# TD_0002-100.net
KiCad netlist of a schematic drawn in Altium Designer
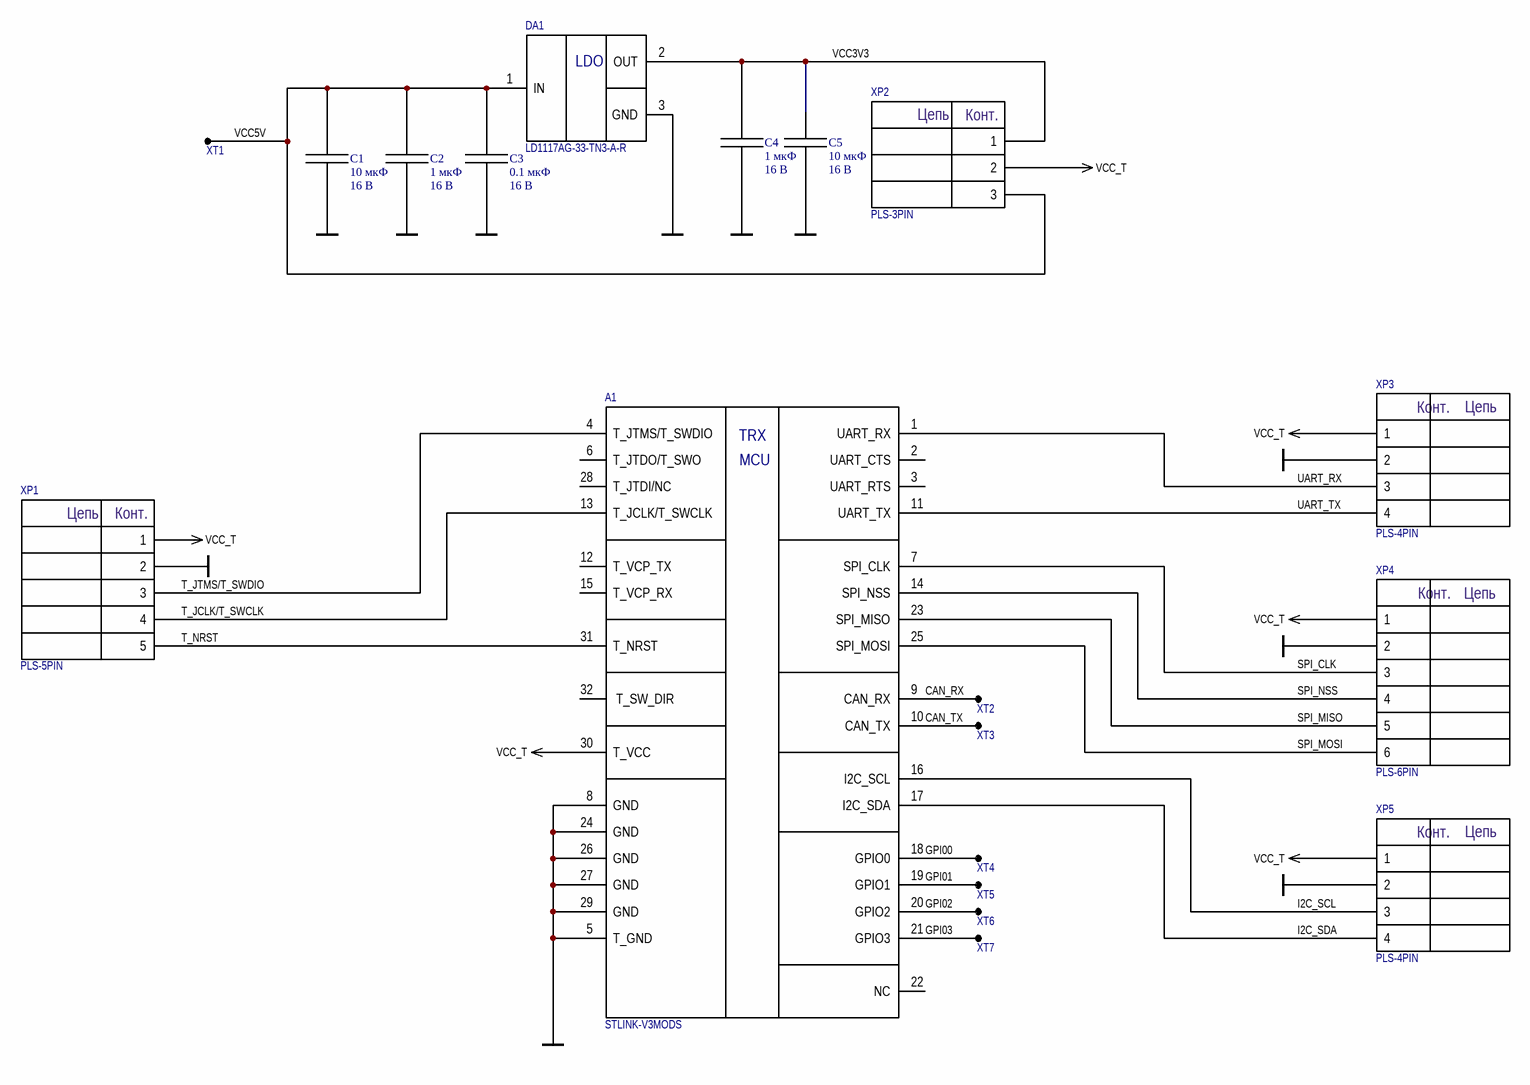
[diagram p0: TD.0002-100.SchDoc]

(export (version "E")
  (design (tool "Eeschema 10.0.6"))
  (components
    (comp (ref "A1")
      (value "STLINK-V3MODS")
      (footprint "STLINK-V3MODS")
      (description "Mini debuggers/programmers for STM32")
      (libsource (lib "FirstLib") (part "STLINK-V3MODS"))
    )
    (comp (ref "C1")
      (value "10 мкФ")
      (footprint "C_0603")
      (description "Chip Monolithic Ceramic Capacitor")
      (fields
        (field (name "PART NUMBER") "GRM188R61C106KAALD")
        (field (name "MANUFACTURER") "Murata")
        (field (name "VOLTAGE") "16 В")
      )
      (libsource (lib "Database_Libs") (part "Capacitor"))
    )
    (comp (ref "C2")
      (value "1 мкФ")
      (footprint "C_0402")
      (description "Chip Multilayer Ceramic Capacitors")
      (fields
        (field (name "PART NUMBER") "GRM155R61C105KA12D")
        (field (name "MANUFACTURER") "Murata")
        (field (name "VOLTAGE") "16 В")
      )
      (libsource (lib "Database_Libs") (part "Capacitor"))
    )
    (comp (ref "C3")
      (value "0.1 мкФ")
      (footprint "C_0402")
      (description "Chip Multilayer Ceramic Capacitors")
      (fields
        (field (name "PART NUMBER") "GRM155R71C104KA88D")
        (field (name "MANUFACTURER") "Murata")
        (field (name "VOLTAGE") "16 В")
      )
      (libsource (lib "Database_Libs") (part "Capacitor"))
    )
    (comp (ref "C4")
      (value "1 мкФ")
      (footprint "C_0402")
      (description "Chip Multilayer Ceramic Capacitors")
      (fields
        (field (name "PART NUMBER") "GRM155R61C105KA12D")
        (field (name "MANUFACTURER") "Murata")
        (field (name "VOLTAGE") "16 В")
      )
      (libsource (lib "Database_Libs") (part "Capacitor"))
    )
    (comp (ref "C5")
      (value "10 мкФ")
      (footprint "C_0603")
      (description "Chip Monolithic Ceramic Capacitor")
      (fields
        (field (name "PART NUMBER") "GRM188R61C106KAALD")
        (field (name "MANUFACTURER") "Murata")
        (field (name "VOLTAGE") "16 В")
      )
      (libsource (lib "Database_Libs") (part "Capacitor"))
    )
    (comp (ref "DA1")
      (value "LD1117AG-33-TN3-A-R")
      (footprint "TO-252")
      (description "Low drop fixed and adjustable positive voltage regulators")
      (libsource (lib "FirstLib") (part "LD1117AG-33-TN3-A-R"))
    )
    (comp (ref "XP1")
      (value "PLS-5PIN")
      (footprint "PLS-5PIN")
      (libsource (lib "FirstLib") (part "PLS-5PIN"))
    )
    (comp (ref "XP2")
      (value "PLS-3PIN")
      (footprint "PLS-3PIN")
      (libsource (lib "FirstLib") (part "PLS-3PIN"))
    )
    (comp (ref "XP3")
      (value "PLS-4PIN")
      (footprint "PLS-4PIN")
      (libsource (lib "FirstLib") (part "PLS-4PIN"))
    )
    (comp (ref "XP4")
      (value "PLS-6PIN")
      (footprint "PLS-6PIN")
      (libsource (lib "FirstLib") (part "PLS-6PIN"))
    )
    (comp (ref "XP5")
      (value "PLS-4PIN")
      (footprint "PLS-4PIN")
      (libsource (lib "FirstLib") (part "PLS-4PIN"))
    )
    (comp (ref "XT1")
      (value "pad")
      (footprint "FirstLib:PAD_2X2mm")
      (libsource (lib "FirstLib") (part "pad"))
    )
    (comp (ref "XT2") (value "pad") (footprint "pad_3x1mm") (libsource (lib "FirstLib") (part "pad")))
    (comp (ref "XT3") (value "pad") (footprint "pad_3x1mm") (libsource (lib "FirstLib") (part "pad")))
    (comp (ref "XT4") (value "pad") (footprint "pad_3x1mm") (libsource (lib "FirstLib") (part "pad")))
    (comp (ref "XT5") (value "pad") (footprint "pad_3x1mm") (libsource (lib "FirstLib") (part "pad")))
    (comp (ref "XT6") (value "pad") (footprint "pad_3x1mm") (libsource (lib "FirstLib") (part "pad")))
    (comp (ref "XT7") (value "pad") (footprint "pad_3x1mm") (libsource (lib "FirstLib") (part "pad")))
  )
  (nets
    (net (code "1") (name "/CAN_RX") (class "Default")
      (node (ref "A1") (pin "9") (pinfunction "CAN_RX_9") (pintype "passive"))
      (node (ref "XT2") (pin "1") (pinfunction "1_1") (pintype "passive"))
    )
    (net (code "2") (name "/CAN_TX") (class "Default")
      (node (ref "A1") (pin "10") (pinfunction "CAN_TX_10") (pintype "passive"))
      (node (ref "XT3") (pin "1") (pinfunction "1_1") (pintype "passive"))
    )
    (net (code "3") (name "/GPI00") (class "Default")
      (node (ref "A1") (pin "18") (pinfunction "GPIO0_18") (pintype "passive"))
      (node (ref "XT4") (pin "1") (pinfunction "1_1") (pintype "passive"))
    )
    (net (code "4") (name "/GPI01") (class "Default")
      (node (ref "A1") (pin "19") (pinfunction "GPIO1_19") (pintype "passive"))
      (node (ref "XT5") (pin "1") (pinfunction "1_1") (pintype "passive"))
    )
    (net (code "5") (name "/GPI02") (class "Default")
      (node (ref "A1") (pin "20") (pinfunction "GPIO2_20") (pintype "passive"))
      (node (ref "XT6") (pin "1") (pinfunction "1_1") (pintype "passive"))
    )
    (net (code "6") (name "/GPI03") (class "Default")
      (node (ref "A1") (pin "21") (pinfunction "GPIO3_21") (pintype "passive"))
      (node (ref "XT7") (pin "1") (pinfunction "1_1") (pintype "passive"))
    )
    (net (code "7") (name "/I2C_SCL") (class "Default")
      (node (ref "A1") (pin "16") (pinfunction "I2C_SCL_16") (pintype "passive"))
      (node (ref "XP5") (pin "3") (pinfunction "3_3") (pintype "passive"))
    )
    (net (code "8") (name "/I2C_SDA") (class "Default")
      (node (ref "A1") (pin "17") (pinfunction "I2C_SDA_17") (pintype "passive"))
      (node (ref "XP5") (pin "4") (pinfunction "4_4") (pintype "passive"))
    )
    (net (code "9") (name "/SPI_CLK") (class "Default")
      (node (ref "A1") (pin "7") (pinfunction "SPI_CLK_7") (pintype "passive"))
      (node (ref "XP4") (pin "3") (pinfunction "3_3") (pintype "passive"))
    )
    (net (code "10") (name "/SPI_MISO") (class "Default")
      (node (ref "A1") (pin "23") (pinfunction "SPI_MISO_23") (pintype "passive"))
      (node (ref "XP4") (pin "5") (pinfunction "5_5") (pintype "passive"))
    )
    (net (code "11") (name "/SPI_MOSI") (class "Default")
      (node (ref "A1") (pin "25") (pinfunction "SPI_MOSI_25") (pintype "passive"))
      (node (ref "XP4") (pin "6") (pinfunction "6_6") (pintype "passive"))
    )
    (net (code "12") (name "/SPI_NSS") (class "Default")
      (node (ref "A1") (pin "14") (pinfunction "SPI_NSS_14") (pintype "passive"))
      (node (ref "XP4") (pin "4") (pinfunction "4_4") (pintype "passive"))
    )
    (net (code "13") (name "/T_JCLK{slash}T_SWCLK") (class "Default")
      (node (ref "A1") (pin "13") (pinfunction "T_JCLK/T_SWCLK_13") (pintype "passive"))
      (node (ref "XP1") (pin "4") (pinfunction "4_4") (pintype "passive"))
    )
    (net (code "14") (name "/T_JTMS{slash}T_SWDIO") (class "Default")
      (node (ref "A1") (pin "4") (pinfunction "T_JTMS/T_SWDIO_4") (pintype "passive"))
      (node (ref "XP1") (pin "3") (pinfunction "3_3") (pintype "passive"))
    )
    (net (code "15") (name "/T_NRST") (class "Default")
      (node (ref "A1") (pin "31") (pinfunction "T_NRST_31") (pintype "passive"))
      (node (ref "XP1") (pin "5") (pinfunction "5_5") (pintype "passive"))
    )
    (net (code "16") (name "/UART_RX") (class "Default")
      (node (ref "A1") (pin "1") (pinfunction "UART_RX_1") (pintype "passive"))
      (node (ref "XP3") (pin "3") (pinfunction "3_3") (pintype "passive"))
    )
    (net (code "17") (name "/UART_TX") (class "Default")
      (node (ref "A1") (pin "11") (pinfunction "UART_TX_11") (pintype "passive"))
      (node (ref "XP3") (pin "4") (pinfunction "4_4") (pintype "passive"))
    )
    (net (code "18") (name "/VCC3V3") (class "Default")
      (node (ref "C4") (pin "1") (pinfunction "1_1") (pintype "passive"))
      (node (ref "C5") (pin "1") (pinfunction "1_1") (pintype "passive"))
      (node (ref "DA1") (pin "2") (pinfunction "OUT_2") (pintype "passive"))
      (node (ref "XP2") (pin "1") (pinfunction "1_1") (pintype "passive"))
    )
    (net (code "19") (name "/VCC5V") (class "Default")
      (node (ref "C1") (pin "1") (pinfunction "1_1") (pintype "passive"))
      (node (ref "C2") (pin "1") (pinfunction "1_1") (pintype "passive"))
      (node (ref "C3") (pin "1") (pinfunction "1_1") (pintype "passive"))
      (node (ref "DA1") (pin "1") (pinfunction "IN_1") (pintype "passive"))
      (node (ref "XP2") (pin "3") (pinfunction "3_3") (pintype "passive"))
      (node (ref "XT1") (pin "1") (pinfunction "1_1") (pintype "passive"))
    )
    (net (code "20") (name "GND") (class "Default")
      (node (ref "A1") (pin "24") (pinfunction "GND_24") (pintype "passive"))
      (node (ref "A1") (pin "26") (pinfunction "GND_26") (pintype "passive"))
      (node (ref "A1") (pin "27") (pinfunction "GND_27") (pintype "passive"))
      (node (ref "A1") (pin "29") (pinfunction "GND_29") (pintype "passive"))
      (node (ref "A1") (pin "5") (pinfunction "T_GND_5") (pintype "passive"))
      (node (ref "A1") (pin "8") (pinfunction "GND_8") (pintype "passive"))
      (node (ref "C1") (pin "2") (pinfunction "2_2") (pintype "passive"))
      (node (ref "C2") (pin "2") (pinfunction "2_2") (pintype "passive"))
      (node (ref "C3") (pin "2") (pinfunction "2_2") (pintype "passive"))
      (node (ref "C4") (pin "2") (pinfunction "2_2") (pintype "passive"))
      (node (ref "C5") (pin "2") (pinfunction "2_2") (pintype "passive"))
      (node (ref "DA1") (pin "3") (pinfunction "GND_3") (pintype "passive"))
      (node (ref "XP1") (pin "2") (pinfunction "2_2") (pintype "passive"))
      (node (ref "XP3") (pin "2") (pinfunction "2_2") (pintype "passive"))
      (node (ref "XP4") (pin "2") (pinfunction "2_2") (pintype "passive"))
      (node (ref "XP5") (pin "2") (pinfunction "2_2") (pintype "passive"))
    )
    (net (code "21") (name "VCC_T") (class "Default")
      (node (ref "A1") (pin "30") (pinfunction "T_VCC_30") (pintype "passive"))
      (node (ref "XP1") (pin "1") (pinfunction "1_1") (pintype "passive"))
      (node (ref "XP2") (pin "2") (pinfunction "2_2") (pintype "passive"))
      (node (ref "XP3") (pin "1") (pinfunction "1_1") (pintype "passive"))
      (node (ref "XP4") (pin "1") (pinfunction "1_1") (pintype "passive"))
      (node (ref "XP5") (pin "1") (pinfunction "1_1") (pintype "passive"))
    )
    (net (code "22") (name "unconnected-(A1-NC-Pad22)") (class "Default")
      (node (ref "A1") (pin "22") (pinfunction "NC_22") (pintype "passive"))
    )
    (net (code "23") (name "unconnected-(A1-T_JTDI{slash}NC-Pad28)") (class "Default")
      (node (ref "A1") (pin "28") (pinfunction "T_JTDI/NC_28") (pintype "passive"))
    )
    (net (code "24") (name "unconnected-(A1-T_JTDO{slash}T_SWO-Pad6)") (class "Default")
      (node (ref "A1") (pin "6") (pinfunction "T_JTDO/T_SWO_6") (pintype "passive"))
    )
    (net (code "25") (name "unconnected-(A1-T_VCP_RX-Pad15)") (class "Default")
      (node (ref "A1") (pin "15") (pinfunction "T_VCP_RX_15") (pintype "passive"))
    )
    (net (code "26") (name "unconnected-(A1-T_VCP_TX-Pad12)") (class "Default")
      (node (ref "A1") (pin "12") (pinfunction "T_VCP_TX_12") (pintype "passive"))
    )
    (net (code "27") (name "unconnected-(A1-UART_CTS-Pad2)") (class "Default")
      (node (ref "A1") (pin "2") (pinfunction "UART_CTS_2") (pintype "passive"))
    )
    (net (code "28") (name "unconnected-(A1-UART_RTS-Pad3)") (class "Default")
      (node (ref "A1") (pin "3") (pinfunction "UART_RTS_3") (pintype "passive"))
    )
    (net (code "29") (name "unconnected-(A1-_T_SW_DIR-Pad32)") (class "Default")
      (node (ref "A1") (pin "32") (pinfunction "_T_SW_DIR_32") (pintype "passive"))
    )
  )
)
